# PANS.net
KiCad netlist of a schematic drawn in EAGLE
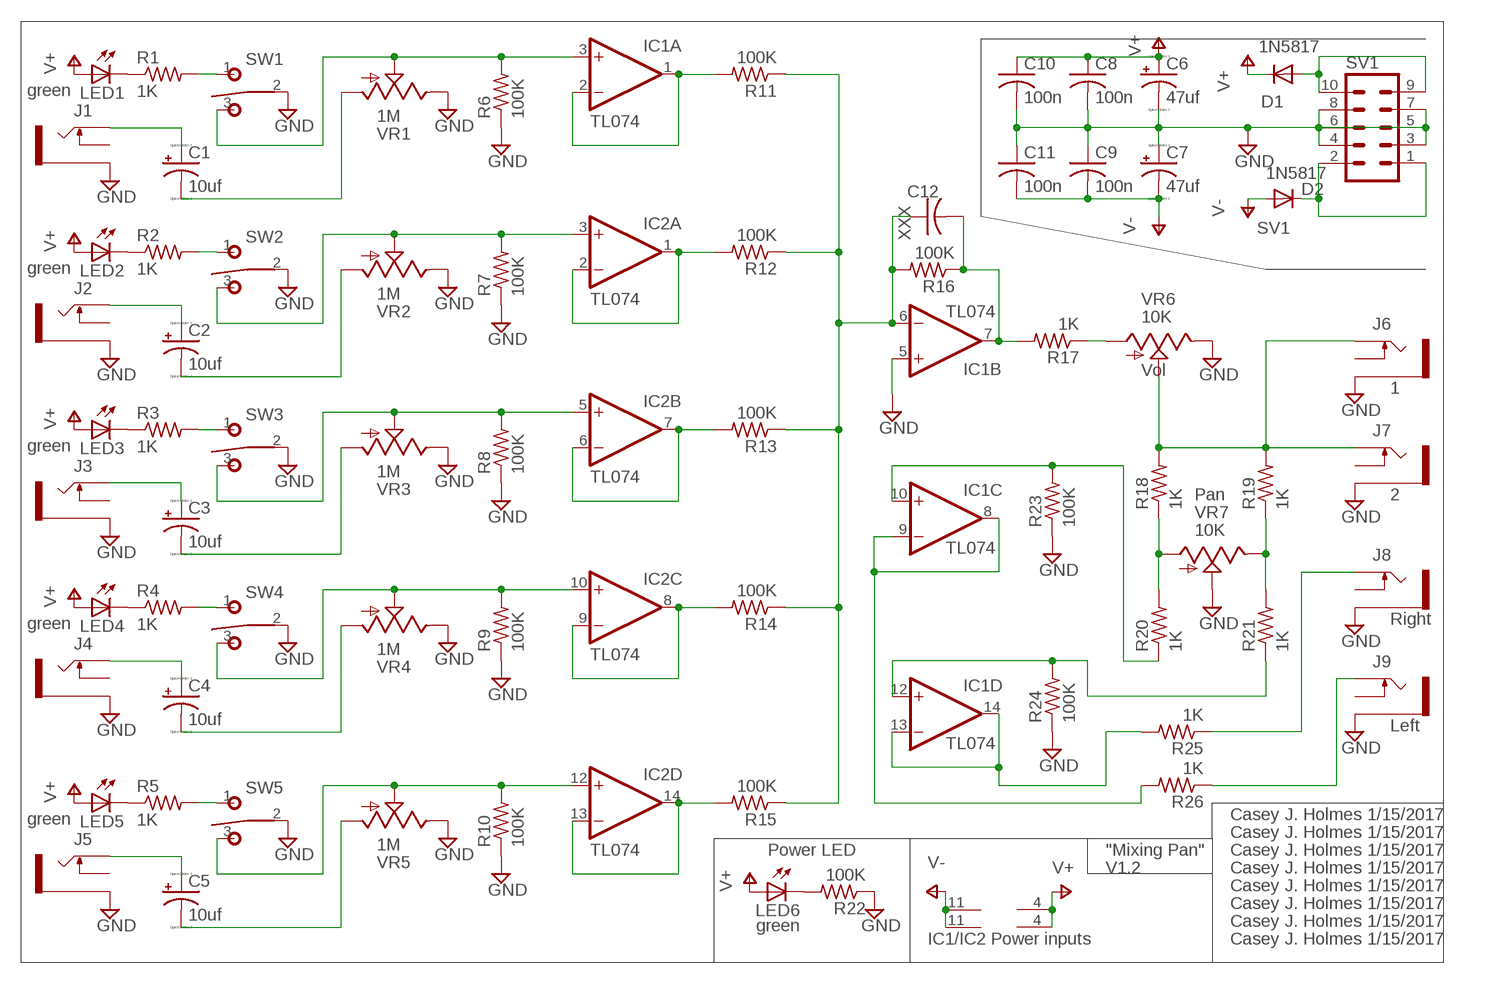
[diagram p0: schematic, sheet 1]

(export (version "E")
  (design (tool "Eeschema 10.0.6"))
  (components
    (comp (ref "C1")
      (value "10uf")
      (footprint "eagle-import:153CLV-0405")
      (libsource (lib "eagle-import") (part "CPOL-US153CLV-0405"))
    )
    (comp (ref "C2")
      (value "10uf")
      (footprint "eagle-import:153CLV-0405")
      (libsource (lib "eagle-import") (part "CPOL-US153CLV-0405"))
    )
    (comp (ref "C3")
      (value "10uf")
      (footprint "eagle-import:153CLV-0405")
      (libsource (lib "eagle-import") (part "CPOL-US153CLV-0405"))
    )
    (comp (ref "C4")
      (value "10uf")
      (footprint "eagle-import:153CLV-0405")
      (libsource (lib "eagle-import") (part "CPOL-US153CLV-0405"))
    )
    (comp (ref "C5")
      (value "10uf")
      (footprint "eagle-import:153CLV-0405")
      (libsource (lib "eagle-import") (part "CPOL-US153CLV-0405"))
    )
    (comp (ref "C6")
      (value "47uf")
      (footprint "eagle-import:PANASONIC_D")
      (libsource (lib "eagle-import") (part "CPOL-USD"))
    )
    (comp (ref "C7")
      (value "47uf")
      (footprint "eagle-import:PANASONIC_D")
      (libsource (lib "eagle-import") (part "CPOL-USD"))
    )
    (comp (ref "C8")
      (value "100n")
      (footprint "eagle-import:C0805")
      (libsource (lib "eagle-import") (part "C-USC0805"))
    )
    (comp (ref "C9")
      (value "100n")
      (footprint "eagle-import:C0805")
      (libsource (lib "eagle-import") (part "C-USC0805"))
    )
    (comp (ref "C10")
      (value "100n")
      (footprint "eagle-import:C0805")
      (libsource (lib "eagle-import") (part "C-USC0805"))
    )
    (comp (ref "C11")
      (value "100n")
      (footprint "eagle-import:C0805")
      (libsource (lib "eagle-import") (part "C-USC0805"))
    )
    (comp (ref "C12")
      (value "XXX")
      (footprint "eagle-import:C0805")
      (libsource (lib "eagle-import") (part "C-USC0805"))
    )
    (comp (ref "D1")
      (value "1N5817")
      (footprint "eagle-import:DO35-7")
      (libsource (lib "eagle-import") (part "SMALL_DIODEDO35-7"))
    )
    (comp (ref "D2")
      (value "1N5817")
      (footprint "eagle-import:DO35-7")
      (libsource (lib "eagle-import") (part "SMALL_DIODEDO35-7"))
    )
    (comp (ref "IC1")
      (value "TL074")
      (footprint "eagle-import:SO14")
      (libsource (lib "eagle-import") (part "TL074_SMD"))
    )
    (comp (ref "IC2")
      (value "TL074")
      (footprint "eagle-import:SO14")
      (libsource (lib "eagle-import") (part "TL074_SMD"))
    )
    (comp (ref "J1")
      (value "THONKICONNOLD")
      (footprint "eagle-import:THONKICONN")
      (libsource (lib "eagle-import") (part "THONKICONNOLD"))
    )
    (comp (ref "J2")
      (value "THONKICONNOLD")
      (footprint "eagle-import:THONKICONN")
      (libsource (lib "eagle-import") (part "THONKICONNOLD"))
    )
    (comp (ref "J3")
      (value "THONKICONNOLD")
      (footprint "eagle-import:THONKICONN")
      (libsource (lib "eagle-import") (part "THONKICONNOLD"))
    )
    (comp (ref "J4")
      (value "THONKICONNOLD")
      (footprint "eagle-import:THONKICONN")
      (libsource (lib "eagle-import") (part "THONKICONNOLD"))
    )
    (comp (ref "J5")
      (value "THONKICONNOLD")
      (footprint "eagle-import:THONKICONN")
      (libsource (lib "eagle-import") (part "THONKICONNOLD"))
    )
    (comp (ref "J6")
      (value "THONKICONNOLD")
      (footprint "eagle-import:THONKICONN")
      (libsource (lib "eagle-import") (part "THONKICONNOLD"))
    )
    (comp (ref "J7")
      (value "THONKICONNOLD")
      (footprint "eagle-import:THONKICONN")
      (libsource (lib "eagle-import") (part "THONKICONNOLD"))
    )
    (comp (ref "J8")
      (value "THONKICONNOLD")
      (footprint "eagle-import:THONKICONN")
      (libsource (lib "eagle-import") (part "THONKICONNOLD"))
    )
    (comp (ref "J9")
      (value "THONKICONNOLD")
      (footprint "eagle-import:THONKICONN")
      (libsource (lib "eagle-import") (part "THONKICONNOLD"))
    )
    (comp (ref "LED1")
      (value "green")
      (footprint "eagle-import:LED5MM")
      (libsource (lib "eagle-import") (part "LED5MM"))
    )
    (comp (ref "LED2")
      (value "green")
      (footprint "eagle-import:LED5MM")
      (libsource (lib "eagle-import") (part "LED5MM"))
    )
    (comp (ref "LED3")
      (value "green")
      (footprint "eagle-import:LED5MM")
      (libsource (lib "eagle-import") (part "LED5MM"))
    )
    (comp (ref "LED4")
      (value "green")
      (footprint "eagle-import:LED5MM")
      (libsource (lib "eagle-import") (part "LED5MM"))
    )
    (comp (ref "LED5")
      (value "green")
      (footprint "eagle-import:LED5MM")
      (libsource (lib "eagle-import") (part "LED5MM"))
    )
    (comp (ref "LED6")
      (value "green")
      (footprint "eagle-import:LED5MM")
      (libsource (lib "eagle-import") (part "LED5MM"))
    )
    (comp (ref "R1")
      (value "1K")
      (footprint "eagle-import:M0805")
      (libsource (lib "eagle-import") (part "R-US_M0805"))
    )
    (comp (ref "R2")
      (value "1K")
      (footprint "eagle-import:M0805")
      (libsource (lib "eagle-import") (part "R-US_M0805"))
    )
    (comp (ref "R3")
      (value "1K")
      (footprint "eagle-import:M0805")
      (libsource (lib "eagle-import") (part "R-US_M0805"))
    )
    (comp (ref "R4")
      (value "1K")
      (footprint "eagle-import:M0805")
      (libsource (lib "eagle-import") (part "R-US_M0805"))
    )
    (comp (ref "R5")
      (value "1K")
      (footprint "eagle-import:M0805")
      (libsource (lib "eagle-import") (part "R-US_M0805"))
    )
    (comp (ref "R6")
      (value "100K")
      (footprint "eagle-import:M0805")
      (libsource (lib "eagle-import") (part "R-US_M0805"))
    )
    (comp (ref "R7")
      (value "100K")
      (footprint "eagle-import:M0805")
      (libsource (lib "eagle-import") (part "R-US_M0805"))
    )
    (comp (ref "R8")
      (value "100K")
      (footprint "eagle-import:M0805")
      (libsource (lib "eagle-import") (part "R-US_M0805"))
    )
    (comp (ref "R9")
      (value "100K")
      (footprint "eagle-import:M0805")
      (libsource (lib "eagle-import") (part "R-US_M0805"))
    )
    (comp (ref "R10")
      (value "100K")
      (footprint "eagle-import:M0805")
      (libsource (lib "eagle-import") (part "R-US_M0805"))
    )
    (comp (ref "R11")
      (value "100K")
      (footprint "eagle-import:M0805")
      (libsource (lib "eagle-import") (part "R-US_M0805"))
    )
    (comp (ref "R12")
      (value "100K")
      (footprint "eagle-import:M0805")
      (libsource (lib "eagle-import") (part "R-US_M0805"))
    )
    (comp (ref "R13")
      (value "100K")
      (footprint "eagle-import:M0805")
      (libsource (lib "eagle-import") (part "R-US_M0805"))
    )
    (comp (ref "R14")
      (value "100K")
      (footprint "eagle-import:M0805")
      (libsource (lib "eagle-import") (part "R-US_M0805"))
    )
    (comp (ref "R15")
      (value "100K")
      (footprint "eagle-import:M0805")
      (libsource (lib "eagle-import") (part "R-US_M0805"))
    )
    (comp (ref "R16")
      (value "100K")
      (footprint "eagle-import:M0805")
      (libsource (lib "eagle-import") (part "R-US_M0805"))
    )
    (comp (ref "R17")
      (value "1K")
      (footprint "eagle-import:M0805")
      (libsource (lib "eagle-import") (part "R-US_M0805"))
    )
    (comp (ref "R18")
      (value "1K")
      (footprint "eagle-import:M0805")
      (libsource (lib "eagle-import") (part "R-US_M0805"))
    )
    (comp (ref "R19")
      (value "1K")
      (footprint "eagle-import:M0805")
      (libsource (lib "eagle-import") (part "R-US_M0805"))
    )
    (comp (ref "R20")
      (value "1K")
      (footprint "eagle-import:M0805")
      (libsource (lib "eagle-import") (part "R-US_M0805"))
    )
    (comp (ref "R21")
      (value "1K")
      (footprint "eagle-import:M0805")
      (libsource (lib "eagle-import") (part "R-US_M0805"))
    )
    (comp (ref "R22")
      (value "100K")
      (footprint "eagle-import:M0805")
      (libsource (lib "eagle-import") (part "R-US_M0805"))
    )
    (comp (ref "R23")
      (value "100K")
      (footprint "eagle-import:M0805")
      (libsource (lib "eagle-import") (part "R-US_M0805"))
    )
    (comp (ref "R24")
      (value "100K")
      (footprint "eagle-import:M0805")
      (libsource (lib "eagle-import") (part "R-US_M0805"))
    )
    (comp (ref "R25")
      (value "1K")
      (footprint "eagle-import:M0805")
      (libsource (lib "eagle-import") (part "R-US_M0805"))
    )
    (comp (ref "R26")
      (value "1K")
      (footprint "eagle-import:M0805")
      (libsource (lib "eagle-import") (part "R-US_M0805"))
    )
    (comp (ref "SV1")
      (value "SV1")
      (footprint "eagle-import:EURO_PWR_HEADER_FAT")
      (libsource (lib "eagle-import") (part "EURO_POWER_HEADERFAT_PADS"))
    )
    (comp (ref "SW1")
      (value "on/on")
      (footprint "eagle-import:M9040P")
      (libsource (lib "eagle-import") (part "T-80-T-SPDT-ON-OFF-ON"))
    )
    (comp (ref "SW2")
      (value "on/on")
      (footprint "eagle-import:M9040P")
      (libsource (lib "eagle-import") (part "T-80-T-SPDT-ON-OFF-ON"))
    )
    (comp (ref "SW3")
      (value "on/on")
      (footprint "eagle-import:M9040P")
      (libsource (lib "eagle-import") (part "T-80-T-SPDT-ON-OFF-ON"))
    )
    (comp (ref "SW4")
      (value "on/on")
      (footprint "eagle-import:M9040P")
      (libsource (lib "eagle-import") (part "T-80-T-SPDT-ON-OFF-ON"))
    )
    (comp (ref "SW5")
      (value "on/on")
      (footprint "eagle-import:M9040P")
      (libsource (lib "eagle-import") (part "T-80-T-SPDT-ON-OFF-ON"))
    )
    (comp (ref "VR1")
      (value "1M")
      (footprint "eagle-import:9MM_SNAP-IN_POT")
      (libsource (lib "eagle-import") (part "9MM_SNAP-IN_POT_"))
    )
    (comp (ref "VR2")
      (value "1M")
      (footprint "eagle-import:9MM_SNAP-IN_POT")
      (libsource (lib "eagle-import") (part "9MM_SNAP-IN_POT_"))
    )
    (comp (ref "VR3")
      (value "1M")
      (footprint "eagle-import:9MM_SNAP-IN_POT")
      (libsource (lib "eagle-import") (part "9MM_SNAP-IN_POT_"))
    )
    (comp (ref "VR4")
      (value "1M")
      (footprint "eagle-import:9MM_SNAP-IN_POT")
      (libsource (lib "eagle-import") (part "9MM_SNAP-IN_POT_"))
    )
    (comp (ref "VR5")
      (value "1M")
      (footprint "eagle-import:9MM_SNAP-IN_POT")
      (libsource (lib "eagle-import") (part "9MM_SNAP-IN_POT_"))
    )
    (comp (ref "VR6")
      (value "10K")
      (footprint "eagle-import:9MM_SNAP-IN_POT")
      (libsource (lib "eagle-import") (part "9MM_SNAP-IN_POT_"))
    )
    (comp (ref "VR7")
      (value "10K")
      (footprint "eagle-import:9MM_SNAP-IN_POT")
      (libsource (lib "eagle-import") (part "9MM_SNAP-IN_POT_"))
    )
  )
  (nets
    (net (code "1") (name "GND") (class "Default")
      (node (ref "C10") (pin "2") (pinfunction "2_2") (pintype "passive"))
      (node (ref "C11") (pin "1") (pinfunction "1_1") (pintype "passive"))
      (node (ref "C6") (pin "-") (pinfunction "-_-") (pintype "passive"))
      (node (ref "C7") (pin "+") (pinfunction "+_+") (pintype "passive"))
      (node (ref "C8") (pin "2") (pinfunction "2_2") (pintype "passive"))
      (node (ref "C9") (pin "1") (pinfunction "1_1") (pintype "passive"))
      (node (ref "IC1") (pin "5") (pinfunction "+IN_5") (pintype "input"))
      (node (ref "J1") (pin "P$1_SLEEVE") (pinfunction "SLEEVE_P$1_SLEEVE") (pintype "passive"))
      (node (ref "J2") (pin "P$1_SLEEVE") (pinfunction "SLEEVE_P$1_SLEEVE") (pintype "passive"))
      (node (ref "J3") (pin "P$1_SLEEVE") (pinfunction "SLEEVE_P$1_SLEEVE") (pintype "passive"))
      (node (ref "J4") (pin "P$1_SLEEVE") (pinfunction "SLEEVE_P$1_SLEEVE") (pintype "passive"))
      (node (ref "J5") (pin "P$1_SLEEVE") (pinfunction "SLEEVE_P$1_SLEEVE") (pintype "passive"))
      (node (ref "J6") (pin "P$1_SLEEVE") (pinfunction "SLEEVE_P$1_SLEEVE") (pintype "passive"))
      (node (ref "J7") (pin "P$1_SLEEVE") (pinfunction "SLEEVE_P$1_SLEEVE") (pintype "passive"))
      (node (ref "J8") (pin "P$1_SLEEVE") (pinfunction "SLEEVE_P$1_SLEEVE") (pintype "passive"))
      (node (ref "J9") (pin "P$1_SLEEVE") (pinfunction "SLEEVE_P$1_SLEEVE") (pintype "passive"))
      (node (ref "R10") (pin "1") (pinfunction "1_1") (pintype "passive"))
      (node (ref "R22") (pin "1") (pinfunction "1_1") (pintype "passive"))
      (node (ref "R23") (pin "1") (pinfunction "1_1") (pintype "passive"))
      (node (ref "R24") (pin "1") (pinfunction "1_1") (pintype "passive"))
      (node (ref "R6") (pin "1") (pinfunction "1_1") (pintype "passive"))
      (node (ref "R7") (pin "1") (pinfunction "1_1") (pintype "passive"))
      (node (ref "R8") (pin "1") (pinfunction "1_1") (pintype "passive"))
      (node (ref "R9") (pin "1") (pinfunction "1_1") (pintype "passive"))
      (node (ref "SV1") (pin "3") (pinfunction "3_3") (pintype "passive"))
      (node (ref "SV1") (pin "4") (pinfunction "4_4") (pintype "passive"))
      (node (ref "SV1") (pin "5") (pinfunction "5_5") (pintype "passive"))
      (node (ref "SV1") (pin "6") (pinfunction "6_6") (pintype "passive"))
      (node (ref "SV1") (pin "7") (pinfunction "7_7") (pintype "passive"))
      (node (ref "SV1") (pin "8") (pinfunction "8_8") (pintype "passive"))
      (node (ref "SW1") (pin "2") (pinfunction "P_2") (pintype "passive"))
      (node (ref "SW2") (pin "2") (pinfunction "P_2") (pintype "passive"))
      (node (ref "SW3") (pin "2") (pinfunction "P_2") (pintype "passive"))
      (node (ref "SW4") (pin "2") (pinfunction "P_2") (pintype "passive"))
      (node (ref "SW5") (pin "2") (pinfunction "P_2") (pintype "passive"))
      (node (ref "VR1") (pin "3") (pinfunction "E_3") (pintype "passive"))
      (node (ref "VR2") (pin "3") (pinfunction "E_3") (pintype "passive"))
      (node (ref "VR3") (pin "3") (pinfunction "E_3") (pintype "passive"))
      (node (ref "VR4") (pin "3") (pinfunction "E_3") (pintype "passive"))
      (node (ref "VR5") (pin "3") (pinfunction "E_3") (pintype "passive"))
      (node (ref "VR6") (pin "3") (pinfunction "E_3") (pintype "passive"))
      (node (ref "VR7") (pin "2") (pinfunction "S_2") (pintype "passive"))
    )
    (net (code "2") (name "Net-(D1-PadA)") (class "Default")
      (node (ref "D1") (pin "A") (pinfunction "A_A") (pintype "passive"))
      (node (ref "SV1") (pin "10") (pinfunction "10_10") (pintype "passive"))
      (node (ref "SV1") (pin "9") (pinfunction "9_9") (pintype "passive"))
    )
    (net (code "3") (name "Net-(D2-PadC)") (class "Default")
      (node (ref "D2") (pin "C") (pinfunction "C_C") (pintype "passive"))
      (node (ref "SV1") (pin "1") (pinfunction "1_1") (pintype "passive"))
      (node (ref "SV1") (pin "2") (pinfunction "2_2") (pintype "passive"))
    )
    (net (code "4") (name "Net-(IC1A-+IN)") (class "Default")
      (node (ref "IC1") (pin "3") (pinfunction "+IN_3") (pintype "input"))
      (node (ref "R6") (pin "2") (pinfunction "2_2") (pintype "passive"))
      (node (ref "SW1") (pin "3") (pinfunction "S_3") (pintype "passive"))
      (node (ref "VR1") (pin "2") (pinfunction "S_2") (pintype "passive"))
    )
    (net (code "5") (name "Net-(IC1A--IN)") (class "Default")
      (node (ref "IC1") (pin "1") (pinfunction "OUT_1") (pintype "output"))
      (node (ref "IC1") (pin "2") (pinfunction "-IN_2") (pintype "input"))
      (node (ref "R11") (pin "2") (pinfunction "2_2") (pintype "passive"))
    )
    (net (code "6") (name "Net-(IC1B--IN)") (class "Default")
      (node (ref "C12") (pin "1") (pinfunction "1_1") (pintype "passive"))
      (node (ref "IC1") (pin "6") (pinfunction "-IN_6") (pintype "input"))
      (node (ref "R11") (pin "1") (pinfunction "1_1") (pintype "passive"))
      (node (ref "R12") (pin "1") (pinfunction "1_1") (pintype "passive"))
      (node (ref "R13") (pin "1") (pinfunction "1_1") (pintype "passive"))
      (node (ref "R14") (pin "1") (pinfunction "1_1") (pintype "passive"))
      (node (ref "R15") (pin "1") (pinfunction "1_1") (pintype "passive"))
      (node (ref "R16") (pin "2") (pinfunction "2_2") (pintype "passive"))
    )
    (net (code "7") (name "Net-(IC1B-OUT)") (class "Default")
      (node (ref "C12") (pin "2") (pinfunction "2_2") (pintype "passive"))
      (node (ref "IC1") (pin "7") (pinfunction "OUT_7") (pintype "output"))
      (node (ref "R16") (pin "1") (pinfunction "1_1") (pintype "passive"))
      (node (ref "R17") (pin "2") (pinfunction "2_2") (pintype "passive"))
    )
    (net (code "8") (name "Net-(IC1C-+IN)") (class "Default")
      (node (ref "IC1") (pin "10") (pinfunction "+IN_10") (pintype "input"))
      (node (ref "R20") (pin "1") (pinfunction "1_1") (pintype "passive"))
      (node (ref "R23") (pin "2") (pinfunction "2_2") (pintype "passive"))
    )
    (net (code "9") (name "Net-(IC1C--IN)") (class "Default")
      (node (ref "IC1") (pin "8") (pinfunction "OUT_8") (pintype "output"))
      (node (ref "IC1") (pin "9") (pinfunction "-IN_9") (pintype "input"))
      (node (ref "R26") (pin "2") (pinfunction "2_2") (pintype "passive"))
    )
    (net (code "10") (name "Net-(IC1D-+IN)") (class "Default")
      (node (ref "IC1") (pin "12") (pinfunction "+IN_12") (pintype "input"))
      (node (ref "R21") (pin "1") (pinfunction "1_1") (pintype "passive"))
      (node (ref "R24") (pin "2") (pinfunction "2_2") (pintype "passive"))
    )
    (net (code "11") (name "Net-(IC1D--IN)") (class "Default")
      (node (ref "IC1") (pin "13") (pinfunction "-IN_13") (pintype "input"))
      (node (ref "IC1") (pin "14") (pinfunction "OUT_14") (pintype "output"))
      (node (ref "R25") (pin "2") (pinfunction "2_2") (pintype "passive"))
    )
    (net (code "12") (name "Net-(IC2A-+IN)") (class "Default")
      (node (ref "IC2") (pin "3") (pinfunction "+IN_3") (pintype "input"))
      (node (ref "R7") (pin "2") (pinfunction "2_2") (pintype "passive"))
      (node (ref "SW2") (pin "3") (pinfunction "S_3") (pintype "passive"))
      (node (ref "VR2") (pin "2") (pinfunction "S_2") (pintype "passive"))
    )
    (net (code "13") (name "Net-(IC2A--IN)") (class "Default")
      (node (ref "IC2") (pin "1") (pinfunction "OUT_1") (pintype "output"))
      (node (ref "IC2") (pin "2") (pinfunction "-IN_2") (pintype "input"))
      (node (ref "R12") (pin "2") (pinfunction "2_2") (pintype "passive"))
    )
    (net (code "14") (name "Net-(IC2B-+IN)") (class "Default")
      (node (ref "IC2") (pin "5") (pinfunction "+IN_5") (pintype "input"))
      (node (ref "R8") (pin "2") (pinfunction "2_2") (pintype "passive"))
      (node (ref "SW3") (pin "3") (pinfunction "S_3") (pintype "passive"))
      (node (ref "VR3") (pin "2") (pinfunction "S_2") (pintype "passive"))
    )
    (net (code "15") (name "Net-(IC2B--IN)") (class "Default")
      (node (ref "IC2") (pin "6") (pinfunction "-IN_6") (pintype "input"))
      (node (ref "IC2") (pin "7") (pinfunction "OUT_7") (pintype "output"))
      (node (ref "R13") (pin "2") (pinfunction "2_2") (pintype "passive"))
    )
    (net (code "16") (name "Net-(IC2C-+IN)") (class "Default")
      (node (ref "IC2") (pin "10") (pinfunction "+IN_10") (pintype "input"))
      (node (ref "R9") (pin "2") (pinfunction "2_2") (pintype "passive"))
      (node (ref "SW4") (pin "3") (pinfunction "S_3") (pintype "passive"))
      (node (ref "VR4") (pin "2") (pinfunction "S_2") (pintype "passive"))
    )
    (net (code "17") (name "Net-(IC2C--IN)") (class "Default")
      (node (ref "IC2") (pin "8") (pinfunction "OUT_8") (pintype "output"))
      (node (ref "IC2") (pin "9") (pinfunction "-IN_9") (pintype "input"))
      (node (ref "R14") (pin "2") (pinfunction "2_2") (pintype "passive"))
    )
    (net (code "18") (name "Net-(IC2D-+IN)") (class "Default")
      (node (ref "IC2") (pin "12") (pinfunction "+IN_12") (pintype "input"))
      (node (ref "R10") (pin "2") (pinfunction "2_2") (pintype "passive"))
      (node (ref "SW5") (pin "3") (pinfunction "S_3") (pintype "passive"))
      (node (ref "VR5") (pin "2") (pinfunction "S_2") (pintype "passive"))
    )
    (net (code "19") (name "Net-(IC2D--IN)") (class "Default")
      (node (ref "IC2") (pin "13") (pinfunction "-IN_13") (pintype "input"))
      (node (ref "IC2") (pin "14") (pinfunction "OUT_14") (pintype "output"))
      (node (ref "R15") (pin "2") (pinfunction "2_2") (pintype "passive"))
    )
    (net (code "20") (name "Net-(J1-TIP)") (class "Default")
      (node (ref "C1") (pin "+") (pinfunction "+_+") (pintype "passive"))
      (node (ref "J1") (pin "P$3_TIP") (pinfunction "TIP_P$3_TIP") (pintype "passive"))
    )
    (net (code "21") (name "Net-(J2-TIP)") (class "Default")
      (node (ref "C2") (pin "+") (pinfunction "+_+") (pintype "passive"))
      (node (ref "J2") (pin "P$3_TIP") (pinfunction "TIP_P$3_TIP") (pintype "passive"))
    )
    (net (code "22") (name "Net-(J3-TIP)") (class "Default")
      (node (ref "C3") (pin "+") (pinfunction "+_+") (pintype "passive"))
      (node (ref "J3") (pin "P$3_TIP") (pinfunction "TIP_P$3_TIP") (pintype "passive"))
    )
    (net (code "23") (name "Net-(J4-TIP)") (class "Default")
      (node (ref "C4") (pin "+") (pinfunction "+_+") (pintype "passive"))
      (node (ref "J4") (pin "P$3_TIP") (pinfunction "TIP_P$3_TIP") (pintype "passive"))
    )
    (net (code "24") (name "Net-(J5-TIP)") (class "Default")
      (node (ref "C5") (pin "+") (pinfunction "+_+") (pintype "passive"))
      (node (ref "J5") (pin "P$3_TIP") (pinfunction "TIP_P$3_TIP") (pintype "passive"))
    )
    (net (code "25") (name "Net-(J6-TIP)") (class "Default")
      (node (ref "J6") (pin "P$3_TIP") (pinfunction "TIP_P$3_TIP") (pintype "passive"))
      (node (ref "J7") (pin "P$3_TIP") (pinfunction "TIP_P$3_TIP") (pintype "passive"))
      (node (ref "R18") (pin "2") (pinfunction "2_2") (pintype "passive"))
      (node (ref "R19") (pin "2") (pinfunction "2_2") (pintype "passive"))
      (node (ref "VR6") (pin "2") (pinfunction "S_2") (pintype "passive"))
    )
    (net (code "26") (name "Net-(J8-TIP)") (class "Default")
      (node (ref "J8") (pin "P$3_TIP") (pinfunction "TIP_P$3_TIP") (pintype "passive"))
      (node (ref "R25") (pin "1") (pinfunction "1_1") (pintype "passive"))
    )
    (net (code "27") (name "Net-(J9-TIP)") (class "Default")
      (node (ref "J9") (pin "P$3_TIP") (pinfunction "TIP_P$3_TIP") (pintype "passive"))
      (node (ref "R26") (pin "1") (pinfunction "1_1") (pintype "passive"))
    )
    (net (code "28") (name "Net-(LED1-C)") (class "Default")
      (node (ref "LED1") (pin "K") (pinfunction "C_K") (pintype "passive"))
      (node (ref "R1") (pin "1") (pinfunction "1_1") (pintype "passive"))
    )
    (net (code "29") (name "Net-(LED2-C)") (class "Default")
      (node (ref "LED2") (pin "K") (pinfunction "C_K") (pintype "passive"))
      (node (ref "R2") (pin "1") (pinfunction "1_1") (pintype "passive"))
    )
    (net (code "30") (name "Net-(LED3-C)") (class "Default")
      (node (ref "LED3") (pin "K") (pinfunction "C_K") (pintype "passive"))
      (node (ref "R3") (pin "1") (pinfunction "1_1") (pintype "passive"))
    )
    (net (code "31") (name "Net-(LED4-C)") (class "Default")
      (node (ref "LED4") (pin "K") (pinfunction "C_K") (pintype "passive"))
      (node (ref "R4") (pin "1") (pinfunction "1_1") (pintype "passive"))
    )
    (net (code "32") (name "Net-(LED5-C)") (class "Default")
      (node (ref "LED5") (pin "K") (pinfunction "C_K") (pintype "passive"))
      (node (ref "R5") (pin "1") (pinfunction "1_1") (pintype "passive"))
    )
    (net (code "33") (name "Net-(LED6-C)") (class "Default")
      (node (ref "LED6") (pin "K") (pinfunction "C_K") (pintype "passive"))
      (node (ref "R22") (pin "2") (pinfunction "2_2") (pintype "passive"))
    )
    (net (code "34") (name "Net-(SW1-O)") (class "Default")
      (node (ref "R1") (pin "2") (pinfunction "2_2") (pintype "passive"))
      (node (ref "SW1") (pin "1") (pinfunction "O_1") (pintype "passive"))
    )
    (net (code "35") (name "Net-(SW2-O)") (class "Default")
      (node (ref "R2") (pin "2") (pinfunction "2_2") (pintype "passive"))
      (node (ref "SW2") (pin "1") (pinfunction "O_1") (pintype "passive"))
    )
    (net (code "36") (name "Net-(SW3-O)") (class "Default")
      (node (ref "R3") (pin "2") (pinfunction "2_2") (pintype "passive"))
      (node (ref "SW3") (pin "1") (pinfunction "O_1") (pintype "passive"))
    )
    (net (code "37") (name "Net-(SW4-O)") (class "Default")
      (node (ref "R4") (pin "2") (pinfunction "2_2") (pintype "passive"))
      (node (ref "SW4") (pin "1") (pinfunction "O_1") (pintype "passive"))
    )
    (net (code "38") (name "Net-(SW5-O)") (class "Default")
      (node (ref "R5") (pin "2") (pinfunction "2_2") (pintype "passive"))
      (node (ref "SW5") (pin "1") (pinfunction "O_1") (pintype "passive"))
    )
    (net (code "39") (name "Net-(VR1-A)") (class "Default")
      (node (ref "C1") (pin "-") (pinfunction "-_-") (pintype "passive"))
      (node (ref "VR1") (pin "1") (pinfunction "A_1") (pintype "passive"))
    )
    (net (code "40") (name "Net-(VR2-A)") (class "Default")
      (node (ref "C2") (pin "-") (pinfunction "-_-") (pintype "passive"))
      (node (ref "VR2") (pin "1") (pinfunction "A_1") (pintype "passive"))
    )
    (net (code "41") (name "Net-(VR3-A)") (class "Default")
      (node (ref "C3") (pin "-") (pinfunction "-_-") (pintype "passive"))
      (node (ref "VR3") (pin "1") (pinfunction "A_1") (pintype "passive"))
    )
    (net (code "42") (name "Net-(VR4-A)") (class "Default")
      (node (ref "C4") (pin "-") (pinfunction "-_-") (pintype "passive"))
      (node (ref "VR4") (pin "1") (pinfunction "A_1") (pintype "passive"))
    )
    (net (code "43") (name "Net-(VR5-A)") (class "Default")
      (node (ref "C5") (pin "-") (pinfunction "-_-") (pintype "passive"))
      (node (ref "VR5") (pin "1") (pinfunction "A_1") (pintype "passive"))
    )
    (net (code "44") (name "Net-(VR6-A)") (class "Default")
      (node (ref "R17") (pin "1") (pinfunction "1_1") (pintype "passive"))
      (node (ref "VR6") (pin "1") (pinfunction "A_1") (pintype "passive"))
    )
    (net (code "45") (name "Net-(VR7-A)") (class "Default")
      (node (ref "R18") (pin "1") (pinfunction "1_1") (pintype "passive"))
      (node (ref "R20") (pin "2") (pinfunction "2_2") (pintype "passive"))
      (node (ref "VR7") (pin "1") (pinfunction "A_1") (pintype "passive"))
    )
    (net (code "46") (name "Net-(VR7-E)") (class "Default")
      (node (ref "R19") (pin "1") (pinfunction "1_1") (pintype "passive"))
      (node (ref "R21") (pin "2") (pinfunction "2_2") (pintype "passive"))
      (node (ref "VR7") (pin "3") (pinfunction "E_3") (pintype "passive"))
    )
    (net (code "47") (name "V+") (class "Default")
      (node (ref "C10") (pin "1") (pinfunction "1_1") (pintype "passive"))
      (node (ref "C6") (pin "+") (pinfunction "+_+") (pintype "passive"))
      (node (ref "C8") (pin "1") (pinfunction "1_1") (pintype "passive"))
      (node (ref "D1") (pin "C") (pinfunction "C_C") (pintype "passive"))
      (node (ref "IC1") (pin "4") (pinfunction "V+_4") (pintype "power_in"))
      (node (ref "IC2") (pin "4") (pinfunction "V+_4") (pintype "power_in"))
      (node (ref "LED1") (pin "A") (pinfunction "A_A") (pintype "passive"))
      (node (ref "LED2") (pin "A") (pinfunction "A_A") (pintype "passive"))
      (node (ref "LED3") (pin "A") (pinfunction "A_A") (pintype "passive"))
      (node (ref "LED4") (pin "A") (pinfunction "A_A") (pintype "passive"))
      (node (ref "LED5") (pin "A") (pinfunction "A_A") (pintype "passive"))
      (node (ref "LED6") (pin "A") (pinfunction "A_A") (pintype "passive"))
    )
    (net (code "48") (name "V-") (class "Default")
      (node (ref "C11") (pin "2") (pinfunction "2_2") (pintype "passive"))
      (node (ref "C7") (pin "-") (pinfunction "-_-") (pintype "passive"))
      (node (ref "C9") (pin "2") (pinfunction "2_2") (pintype "passive"))
      (node (ref "D2") (pin "A") (pinfunction "A_A") (pintype "passive"))
      (node (ref "IC1") (pin "11") (pinfunction "V-_11") (pintype "power_in"))
      (node (ref "IC2") (pin "11") (pinfunction "V-_11") (pintype "power_in"))
    )
    (net (code "49") (name "unconnected-(J1-SWITCH-PadP$2_SWITCH)") (class "Default")
      (node (ref "J1") (pin "P$2_SWITCH") (pinfunction "SWITCH_P$2_SWITCH") (pintype "passive"))
    )
    (net (code "50") (name "unconnected-(J2-SWITCH-PadP$2_SWITCH)") (class "Default")
      (node (ref "J2") (pin "P$2_SWITCH") (pinfunction "SWITCH_P$2_SWITCH") (pintype "passive"))
    )
    (net (code "51") (name "unconnected-(J3-SWITCH-PadP$2_SWITCH)") (class "Default")
      (node (ref "J3") (pin "P$2_SWITCH") (pinfunction "SWITCH_P$2_SWITCH") (pintype "passive"))
    )
    (net (code "52") (name "unconnected-(J4-SWITCH-PadP$2_SWITCH)") (class "Default")
      (node (ref "J4") (pin "P$2_SWITCH") (pinfunction "SWITCH_P$2_SWITCH") (pintype "passive"))
    )
    (net (code "53") (name "unconnected-(J5-SWITCH-PadP$2_SWITCH)") (class "Default")
      (node (ref "J5") (pin "P$2_SWITCH") (pinfunction "SWITCH_P$2_SWITCH") (pintype "passive"))
    )
    (net (code "54") (name "unconnected-(J6-SWITCH-PadP$2_SWITCH)") (class "Default")
      (node (ref "J6") (pin "P$2_SWITCH") (pinfunction "SWITCH_P$2_SWITCH") (pintype "passive"))
    )
    (net (code "55") (name "unconnected-(J7-SWITCH-PadP$2_SWITCH)") (class "Default")
      (node (ref "J7") (pin "P$2_SWITCH") (pinfunction "SWITCH_P$2_SWITCH") (pintype "passive"))
    )
    (net (code "56") (name "unconnected-(J8-SWITCH-PadP$2_SWITCH)") (class "Default")
      (node (ref "J8") (pin "P$2_SWITCH") (pinfunction "SWITCH_P$2_SWITCH") (pintype "passive"))
    )
    (net (code "57") (name "unconnected-(J9-SWITCH-PadP$2_SWITCH)") (class "Default")
      (node (ref "J9") (pin "P$2_SWITCH") (pinfunction "SWITCH_P$2_SWITCH") (pintype "passive"))
    )
  )
)
